# Radio.net
KiCad netlist of a schematic drawn in Altium Designer
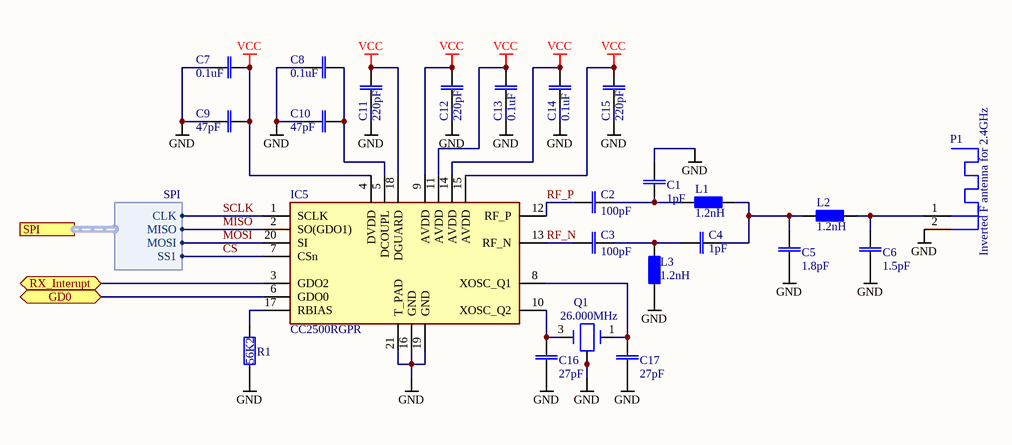
[diagram p0: Radio.SchDoc]

(export (version "E")
  (design (tool "Eeschema 10.0.6"))
  (components
    (comp (ref "C1")
      (value "1pF")
      (footprint "CAP0402")
      (fields (field (name "MANUFACTURER") "Samsung Electro-Mechanics"))
      (libsource (lib "Schematic") (part "CAP_0402"))
    )
    (comp (ref "C2")
      (value "100pF")
      (footprint "CAP0402")
      (fields (field (name "MANUFACTURER") "Samsung Electro-Mechanics"))
      (libsource (lib "Schematic") (part "CAP_0402"))
    )
    (comp (ref "C3")
      (value "100pF")
      (footprint "CAP0402")
      (fields (field (name "MANUFACTURER") "Samsung Electro-Mechanics"))
      (libsource (lib "Schematic") (part "CAP_0402"))
    )
    (comp (ref "C4")
      (value "1pF")
      (footprint "CAP0402")
      (fields (field (name "MANUFACTURER") "Samsung Electro-Mechanics"))
      (libsource (lib "Schematic") (part "CAP_0402"))
    )
    (comp (ref "C5")
      (value "1.8pF")
      (footprint "CAP0402")
      (fields (field (name "MANUFACTURER") "Samsung Electro-Mechanics"))
      (libsource (lib "Schematic") (part "CAP_0402"))
    )
    (comp (ref "C6")
      (value "1.5pF")
      (footprint "CAP0402")
      (fields (field (name "MANUFACTURER") "Samsung Electro-Mechanics"))
      (libsource (lib "Schematic") (part "CAP_0402"))
    )
    (comp (ref "C7")
      (value "0.1uF")
      (footprint "CAP0402")
      (fields (field (name "MANUFACTURER") "Samsung Electro-Mechanics"))
      (libsource (lib "Schematic") (part "CAP_0402"))
    )
    (comp (ref "C8")
      (value "0.1uF")
      (footprint "CAP0402")
      (fields (field (name "MANUFACTURER") "Samsung Electro-Mechanics"))
      (libsource (lib "Schematic") (part "CAP_0402"))
    )
    (comp (ref "C9")
      (value "47pF")
      (footprint "CAP0402")
      (fields (field (name "MANUFACTURER") "Samsung Electro-Mechanics"))
      (libsource (lib "Schematic") (part "CAP_0402"))
    )
    (comp (ref "C10")
      (value "47pF")
      (footprint "CAP0402")
      (fields (field (name "MANUFACTURER") "Samsung Electro-Mechanics"))
      (libsource (lib "Schematic") (part "CAP_0402"))
    )
    (comp (ref "C11")
      (value "220pF")
      (footprint "CAP0402")
      (fields (field (name "MANUFACTURER") "Samsung Electro-Mechanics"))
      (libsource (lib "Schematic") (part "CAP_0402"))
    )
    (comp (ref "C12")
      (value "220pF")
      (footprint "CAP0402")
      (fields (field (name "MANUFACTURER") "Samsung Electro-Mechanics"))
      (libsource (lib "Schematic") (part "CAP_0402"))
    )
    (comp (ref "C13")
      (value "0.1uF")
      (footprint "CAP0402")
      (fields (field (name "MANUFACTURER") "Samsung Electro-Mechanics"))
      (libsource (lib "Schematic") (part "CAP_0402"))
    )
    (comp (ref "C14")
      (value "0.1uF")
      (footprint "CAP0402")
      (fields (field (name "MANUFACTURER") "Samsung Electro-Mechanics"))
      (libsource (lib "Schematic") (part "CAP_0402"))
    )
    (comp (ref "C15")
      (value "220pF")
      (footprint "CAP0402")
      (fields (field (name "MANUFACTURER") "Samsung Electro-Mechanics"))
      (libsource (lib "Schematic") (part "CAP_0402"))
    )
    (comp (ref "C16")
      (value "27pF")
      (footprint "CAP0402")
      (fields (field (name "MANUFACTURER") "Samsung Electro-Mechanics"))
      (libsource (lib "Schematic") (part "CAP_0402"))
    )
    (comp (ref "C17")
      (value "27pF")
      (footprint "CAP0402")
      (fields (field (name "MANUFACTURER") "Samsung Electro-Mechanics"))
      (libsource (lib "Schematic") (part "CAP_0402"))
    )
    (comp (ref "IC5")
      (value "CC2500RGPR")
      (footprint "QFN20_4X4(CC2500)")
      (fields (field (name "MANUFACTURER") "Texas Instruments"))
      (libsource (lib "Schematic") (part "CC2500"))
    )
    (comp (ref "L1")
      (value "1.2nH")
      (footprint "IND0402")
      (fields (field (name "MANUFACTURER") "Abracon LLC"))
      (libsource (lib "Schematic") (part "IND_0402"))
    )
    (comp (ref "L2")
      (value "1.2nH")
      (footprint "IND0402")
      (fields (field (name "MANUFACTURER") "Abracon LLC"))
      (libsource (lib "Schematic") (part "IND_0402"))
    )
    (comp (ref "L3")
      (value "1.2nH")
      (footprint "IND0402")
      (fields (field (name "MANUFACTURER") "Abracon LLC"))
      (libsource (lib "") (part "IND_0402_1"))
    )
    (comp (ref "P1")
      (value "Inverted F antenna for 2.4GHz")
      (footprint "Inverted_F_Antenna_2400MHZ")
      (libsource (lib "Schematic") (part "Antenna F 2400MHz"))
    )
    (comp (ref "Q1")
      (value "26.000MHz")
      (footprint "OSCCC322507")
      (fields (field (name "MANUFACTURER") "Abracon LLC"))
      (libsource (lib "Schematic") (part "ABM8G-26.000MHZ-18-D2Y-T"))
    )
    (comp (ref "R1")
      (value "56K2")
      (footprint "RES0402")
      (fields (field (name "MANUFACTURER") "YAGEO"))
      (libsource (lib "Schematic") (part "RES_0402"))
    )
  )
  (nets
    (net (code "2") (name "/CS") (class "Default")
      (node (ref "IC5") (pin "7") (pinfunction "CSn_7") (pintype "passive"))
    )
    (net (code "3") (name "/GD0") (class "Default")
      (node (ref "IC5") (pin "6") (pinfunction "GDO0_6") (pintype "passive"))
    )
    (net (code "4") (name "/MISO") (class "Default")
      (node (ref "IC5") (pin "2") (pinfunction "SO(GDO1)_2") (pintype "passive"))
    )
    (net (code "5") (name "/MOSI") (class "Default")
      (node (ref "IC5") (pin "20") (pinfunction "SI_20") (pintype "passive"))
    )
    (net (code "6") (name "/RF_N") (class "Default")
      (node (ref "C3") (pin "1") (pinfunction "1_1") (pintype "passive"))
      (node (ref "IC5") (pin "13") (pinfunction "RF_N_13") (pintype "passive"))
    )
    (net (code "7") (name "/RF_P") (class "Default")
      (node (ref "C2") (pin "1") (pinfunction "1_1") (pintype "passive"))
      (node (ref "IC5") (pin "12") (pinfunction "RF_P_12") (pintype "passive"))
    )
    (net (code "8") (name "/RX_Interupt") (class "Default")
      (node (ref "IC5") (pin "3") (pinfunction "GDO2_3") (pintype "passive"))
    )
    (net (code "9") (name "/SCLK") (class "Default")
      (node (ref "IC5") (pin "1") (pinfunction "SCLK_1") (pintype "passive"))
    )
    (net (code "11") (name "GND") (class "Default")
      (node (ref "C1") (pin "1") (pinfunction "1_1") (pintype "passive"))
      (node (ref "C10") (pin "1") (pinfunction "1_1") (pintype "passive"))
      (node (ref "C11") (pin "1") (pinfunction "1_1") (pintype "passive"))
      (node (ref "C12") (pin "1") (pinfunction "1_1") (pintype "passive"))
      (node (ref "C13") (pin "1") (pinfunction "1_1") (pintype "passive"))
      (node (ref "C14") (pin "1") (pinfunction "1_1") (pintype "passive"))
      (node (ref "C15") (pin "1") (pinfunction "1_1") (pintype "passive"))
      (node (ref "C16") (pin "2") (pinfunction "2_2") (pintype "passive"))
      (node (ref "C17") (pin "2") (pinfunction "2_2") (pintype "passive"))
      (node (ref "C5") (pin "2") (pinfunction "2_2") (pintype "passive"))
      (node (ref "C6") (pin "2") (pinfunction "2_2") (pintype "passive"))
      (node (ref "C7") (pin "1") (pinfunction "1_1") (pintype "passive"))
      (node (ref "C8") (pin "1") (pinfunction "1_1") (pintype "passive"))
      (node (ref "C9") (pin "1") (pinfunction "1_1") (pintype "passive"))
      (node (ref "IC5") (pin "16") (pinfunction "GND_16") (pintype "passive"))
      (node (ref "IC5") (pin "19") (pinfunction "GND_19") (pintype "passive"))
      (node (ref "IC5") (pin "21") (pinfunction "T_PAD_21") (pintype "passive"))
      (node (ref "L3") (pin "1") (pinfunction "1_1") (pintype "passive"))
      (node (ref "P1") (pin "2") (pinfunction "REF_2") (pintype "passive"))
      (node (ref "Q1") (pin "2") (pinfunction "2_2") (pintype "passive"))
      (node (ref "Q1") (pin "4") (pinfunction "4_4") (pintype "passive"))
      (node (ref "R1") (pin "1") (pinfunction "1_1") (pintype "passive"))
    )
    (net (code "12") (name "Net-(C1-Pad2)") (class "Default")
      (node (ref "C1") (pin "2") (pinfunction "2_2") (pintype "passive"))
      (node (ref "C2") (pin "2") (pinfunction "2_2") (pintype "passive"))
      (node (ref "L1") (pin "1") (pinfunction "1_1") (pintype "passive"))
    )
    (net (code "13") (name "Net-(C3-Pad2)") (class "Default")
      (node (ref "C3") (pin "2") (pinfunction "2_2") (pintype "passive"))
      (node (ref "C4") (pin "2") (pinfunction "2_2") (pintype "passive"))
      (node (ref "L3") (pin "2") (pinfunction "2_2") (pintype "passive"))
    )
    (net (code "14") (name "Net-(C4-Pad1)") (class "Default")
      (node (ref "C4") (pin "1") (pinfunction "1_1") (pintype "passive"))
      (node (ref "C5") (pin "1") (pinfunction "1_1") (pintype "passive"))
      (node (ref "L1") (pin "2") (pinfunction "2_2") (pintype "passive"))
      (node (ref "L2") (pin "1") (pinfunction "1_1") (pintype "passive"))
    )
    (net (code "15") (name "Net-(IC5-DCOUPL)") (class "Default")
      (node (ref "C10") (pin "2") (pinfunction "2_2") (pintype "passive"))
      (node (ref "C8") (pin "2") (pinfunction "2_2") (pintype "passive"))
      (node (ref "IC5") (pin "5") (pinfunction "DCOUPL_5") (pintype "passive"))
    )
    (net (code "16") (name "Net-(IC5-RBIAS)") (class "Default")
      (node (ref "IC5") (pin "17") (pinfunction "RBIAS_17") (pintype "passive"))
      (node (ref "R1") (pin "2") (pinfunction "2_2") (pintype "passive"))
    )
    (net (code "17") (name "Net-(IC5-XOSC_Q1)") (class "Default")
      (node (ref "C17") (pin "1") (pinfunction "1_1") (pintype "passive"))
      (node (ref "IC5") (pin "8") (pinfunction "XOSC_Q1_8") (pintype "passive"))
      (node (ref "Q1") (pin "1") (pinfunction "1_1") (pintype "passive"))
    )
    (net (code "18") (name "Net-(IC5-XOSC_Q2)") (class "Default")
      (node (ref "C16") (pin "1") (pinfunction "1_1") (pintype "passive"))
      (node (ref "IC5") (pin "10") (pinfunction "XOSC_Q2_10") (pintype "passive"))
      (node (ref "Q1") (pin "3") (pinfunction "3_3") (pintype "passive"))
    )
    (net (code "19") (name "Net-(P1-FEED)") (class "Default")
      (node (ref "C6") (pin "1") (pinfunction "1_1") (pintype "passive"))
      (node (ref "L2") (pin "2") (pinfunction "2_2") (pintype "passive"))
      (node (ref "P1") (pin "1") (pinfunction "FEED_1") (pintype "passive"))
    )
    (net (code "20") (name "VCC") (class "Default")
      (node (ref "C11") (pin "2") (pinfunction "2_2") (pintype "passive"))
      (node (ref "C12") (pin "2") (pinfunction "2_2") (pintype "passive"))
      (node (ref "C13") (pin "2") (pinfunction "2_2") (pintype "passive"))
      (node (ref "C14") (pin "2") (pinfunction "2_2") (pintype "passive"))
      (node (ref "C15") (pin "2") (pinfunction "2_2") (pintype "passive"))
      (node (ref "C7") (pin "2") (pinfunction "2_2") (pintype "passive"))
      (node (ref "C9") (pin "2") (pinfunction "2_2") (pintype "passive"))
      (node (ref "IC5") (pin "11") (pinfunction "AVDD_11") (pintype "passive"))
      (node (ref "IC5") (pin "14") (pinfunction "AVDD_14") (pintype "passive"))
      (node (ref "IC5") (pin "15") (pinfunction "AVDD_15") (pintype "passive"))
      (node (ref "IC5") (pin "18") (pinfunction "DGUARD_18") (pintype "passive"))
      (node (ref "IC5") (pin "4") (pinfunction "DVDD_4") (pintype "passive"))
      (node (ref "IC5") (pin "9") (pinfunction "AVDD_9") (pintype "passive"))
    )
  )
)
